# SingleTransistor.net
KiCad netlist of a schematic drawn in EAGLE
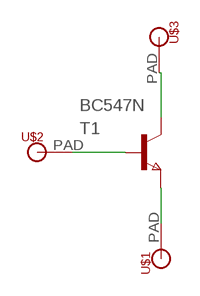
[diagram p0: schematic, sheet 1]

(export (version "E")
  (design (tool "Eeschema 10.0.6"))
  (components
    (comp (ref "T1")
      (value "BC547N")
      (footprint "eagle-import:TO92")
      (fields (field (name "MF") "ON Semiconductor") (field (name "MP") "BC547"))
      (libsource (lib "eagle-import") (part "BC547N"))
    )
    (comp (ref "U$1")
      (value "MICROBIT_PAD")
      (footprint "eagle-import:MICROBIT_PAD")
      (libsource (lib "eagle-import") (part "MICROBIT_PAD"))
    )
    (comp (ref "U$2")
      (value "MICROBIT_PAD")
      (footprint "eagle-import:MICROBIT_PAD")
      (libsource (lib "eagle-import") (part "MICROBIT_PAD"))
    )
    (comp (ref "U$3")
      (value "MICROBIT_PAD")
      (footprint "eagle-import:MICROBIT_PAD")
      (libsource (lib "eagle-import") (part "MICROBIT_PAD"))
    )
  )
  (nets
    (net (code "1") (name "Net-(T1-B)") (class "Default")
      (node (ref "T1") (pin "2") (pinfunction "B_2") (pintype "passive"))
      (node (ref "U$2") (pin "PAD") (pinfunction "P$1_PAD") (pintype "bidirectional"))
    )
    (net (code "2") (name "Net-(T1-C)") (class "Default")
      (node (ref "T1") (pin "1") (pinfunction "C_1") (pintype "passive"))
      (node (ref "U$3") (pin "PAD") (pinfunction "P$1_PAD") (pintype "bidirectional"))
    )
    (net (code "3") (name "Net-(T1-E)") (class "Default")
      (node (ref "T1") (pin "3") (pinfunction "E_3") (pintype "passive"))
      (node (ref "U$1") (pin "PAD") (pinfunction "P$1_PAD") (pintype "bidirectional"))
    )
  )
)
